# cytron_sheild.net
KiCad netlist of a schematic drawn in Altium Designer
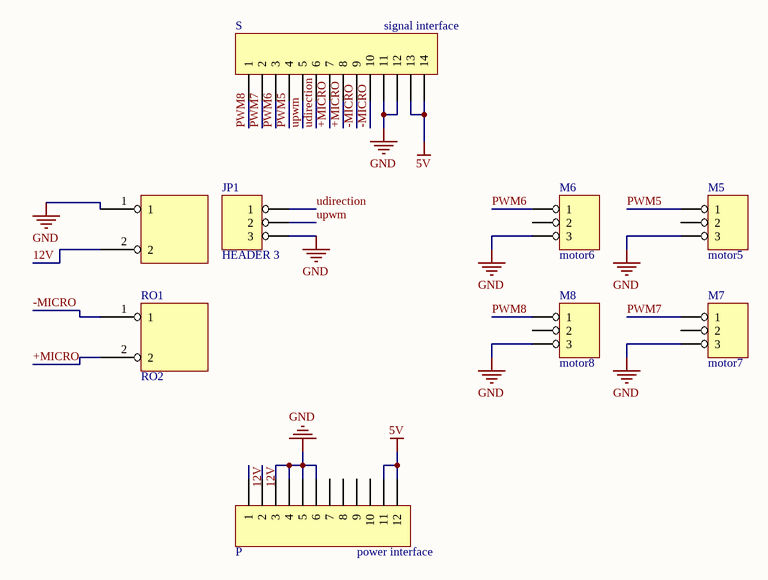
[diagram p0: cytron sheild.SchDoc]

(export (version "E")
  (design (tool "Eeschema 10.0.6"))
  (components
    (comp (ref "JP1") (value "HEADER 3") (footprint "SIP3") (libsource (lib "") (part "HEADER 3_1")))
    (comp (ref "M5") (value "motor5") (footprint "SIP3") (libsource (lib "Final Library") (part "HEADER 3")))
    (comp (ref "M6") (value "motor6") (footprint "SIP3") (libsource (lib "Final Library") (part "HEADER 3")))
    (comp (ref "M7") (value "motor7") (footprint "SIP3") (libsource (lib "Final Library") (part "HEADER 3")))
    (comp (ref "M8") (value "motor8") (footprint "SIP3") (libsource (lib "Final Library") (part "HEADER 3")))
    (comp (ref "P")
      (value "power interface")
      (footprint "HDR1X12")
      (description "Header, 12-Pin")
      (fields (field (name "PUBLISHER") "Altium Limited"))
      (libsource (lib "Miscellaneous Connectors") (part "Header 12"))
    )
    (comp (ref "RO1")
      (value "Rossetta")
      (footprint "Rossetta 2-pin")
      (libsource (lib "crocomarine") (part "Rossetta"))
    )
    (comp (ref "RO2")
      (value "Rossetta")
      (footprint "Rossetta 2-pin")
      (libsource (lib "crocomarine") (part "Rossetta"))
    )
    (comp (ref "S")
      (value "signal interface")
      (footprint "HDR1X14")
      (description "Header, 14-Pin")
      (fields (field (name "PUBLISHER") "Altium Limited"))
      (libsource (lib "Miscellaneous Connectors") (part "Header 14"))
    )
  )
  (nets
    (net (code "1") (name "/+MICRO") (class "Default")
      (node (ref "RO2") (pin "2") (pinfunction "2_2") (pintype "passive"))
      (node (ref "S") (pin "7") (pinfunction "7_7") (pintype "passive"))
      (node (ref "S") (pin "8") (pinfunction "8_8") (pintype "passive"))
    )
    (net (code "2") (name "/-MICRO") (class "Default")
      (node (ref "RO2") (pin "1") (pinfunction "1_1") (pintype "passive"))
      (node (ref "S") (pin "10") (pinfunction "10_10") (pintype "passive"))
      (node (ref "S") (pin "9") (pinfunction "9_9") (pintype "passive"))
    )
    (net (code "3") (name "/12V") (class "Default")
      (node (ref "P") (pin "1") (pinfunction "1_1") (pintype "passive"))
      (node (ref "P") (pin "2") (pinfunction "2_2") (pintype "passive"))
      (node (ref "RO1") (pin "2") (pinfunction "2_2") (pintype "passive"))
    )
    (net (code "4") (name "/PWM5") (class "Default")
      (node (ref "M5") (pin "1") (pinfunction "1_1") (pintype "passive"))
      (node (ref "S") (pin "4") (pinfunction "4_4") (pintype "passive"))
    )
    (net (code "5") (name "/PWM6") (class "Default")
      (node (ref "M6") (pin "1") (pinfunction "1_1") (pintype "passive"))
      (node (ref "S") (pin "3") (pinfunction "3_3") (pintype "passive"))
    )
    (net (code "6") (name "/PWM7") (class "Default")
      (node (ref "M7") (pin "1") (pinfunction "1_1") (pintype "passive"))
      (node (ref "S") (pin "2") (pinfunction "2_2") (pintype "passive"))
    )
    (net (code "7") (name "/PWM8") (class "Default")
      (node (ref "M8") (pin "1") (pinfunction "1_1") (pintype "passive"))
      (node (ref "S") (pin "1") (pinfunction "1_1") (pintype "passive"))
    )
    (net (code "8") (name "/udirection") (class "Default")
      (node (ref "JP1") (pin "1") (pinfunction "1_1") (pintype "passive"))
      (node (ref "S") (pin "6") (pinfunction "6_6") (pintype "passive"))
    )
    (net (code "9") (name "/upwm") (class "Default")
      (node (ref "JP1") (pin "2") (pinfunction "2_2") (pintype "passive"))
      (node (ref "S") (pin "5") (pinfunction "5_5") (pintype "passive"))
    )
    (net (code "10") (name "5V") (class "Default")
      (node (ref "P") (pin "11") (pinfunction "11_11") (pintype "passive"))
      (node (ref "P") (pin "12") (pinfunction "12_12") (pintype "passive"))
      (node (ref "S") (pin "13") (pinfunction "13_13") (pintype "passive"))
      (node (ref "S") (pin "14") (pinfunction "14_14") (pintype "passive"))
    )
    (net (code "11") (name "GND") (class "Default")
      (node (ref "JP1") (pin "3") (pinfunction "3_3") (pintype "passive"))
      (node (ref "M5") (pin "3") (pinfunction "3_3") (pintype "passive"))
      (node (ref "M6") (pin "3") (pinfunction "3_3") (pintype "passive"))
      (node (ref "M7") (pin "3") (pinfunction "3_3") (pintype "passive"))
      (node (ref "M8") (pin "3") (pinfunction "3_3") (pintype "passive"))
      (node (ref "P") (pin "3") (pinfunction "3_3") (pintype "passive"))
      (node (ref "P") (pin "4") (pinfunction "4_4") (pintype "passive"))
      (node (ref "P") (pin "5") (pinfunction "5_5") (pintype "passive"))
      (node (ref "P") (pin "6") (pinfunction "6_6") (pintype "passive"))
      (node (ref "RO1") (pin "1") (pinfunction "1_1") (pintype "passive"))
      (node (ref "S") (pin "11") (pinfunction "11_11") (pintype "passive"))
      (node (ref "S") (pin "12") (pinfunction "12_12") (pintype "passive"))
    )
    (net (code "12") (name "unconnected-(M5-Pad2)") (class "Default")
      (node (ref "M5") (pin "2") (pinfunction "2_2") (pintype "passive"))
    )
    (net (code "13") (name "unconnected-(M6-Pad2)") (class "Default")
      (node (ref "M6") (pin "2") (pinfunction "2_2") (pintype "passive"))
    )
    (net (code "14") (name "unconnected-(M7-Pad2)") (class "Default")
      (node (ref "M7") (pin "2") (pinfunction "2_2") (pintype "passive"))
    )
    (net (code "15") (name "unconnected-(M8-Pad2)") (class "Default")
      (node (ref "M8") (pin "2") (pinfunction "2_2") (pintype "passive"))
    )
    (net (code "16") (name "unconnected-(P-Pad7)") (class "Default")
      (node (ref "P") (pin "7") (pinfunction "7_7") (pintype "passive"))
    )
    (net (code "17") (name "unconnected-(P-Pad8)") (class "Default")
      (node (ref "P") (pin "8") (pinfunction "8_8") (pintype "passive"))
    )
    (net (code "18") (name "unconnected-(P-Pad9)") (class "Default")
      (node (ref "P") (pin "9") (pinfunction "9_9") (pintype "passive"))
    )
    (net (code "19") (name "unconnected-(P-Pad10)") (class "Default")
      (node (ref "P") (pin "10") (pinfunction "10_10") (pintype "passive"))
    )
  )
)
